# trsv_main.net
KiCad netlist of a schematic drawn in Altium Designer
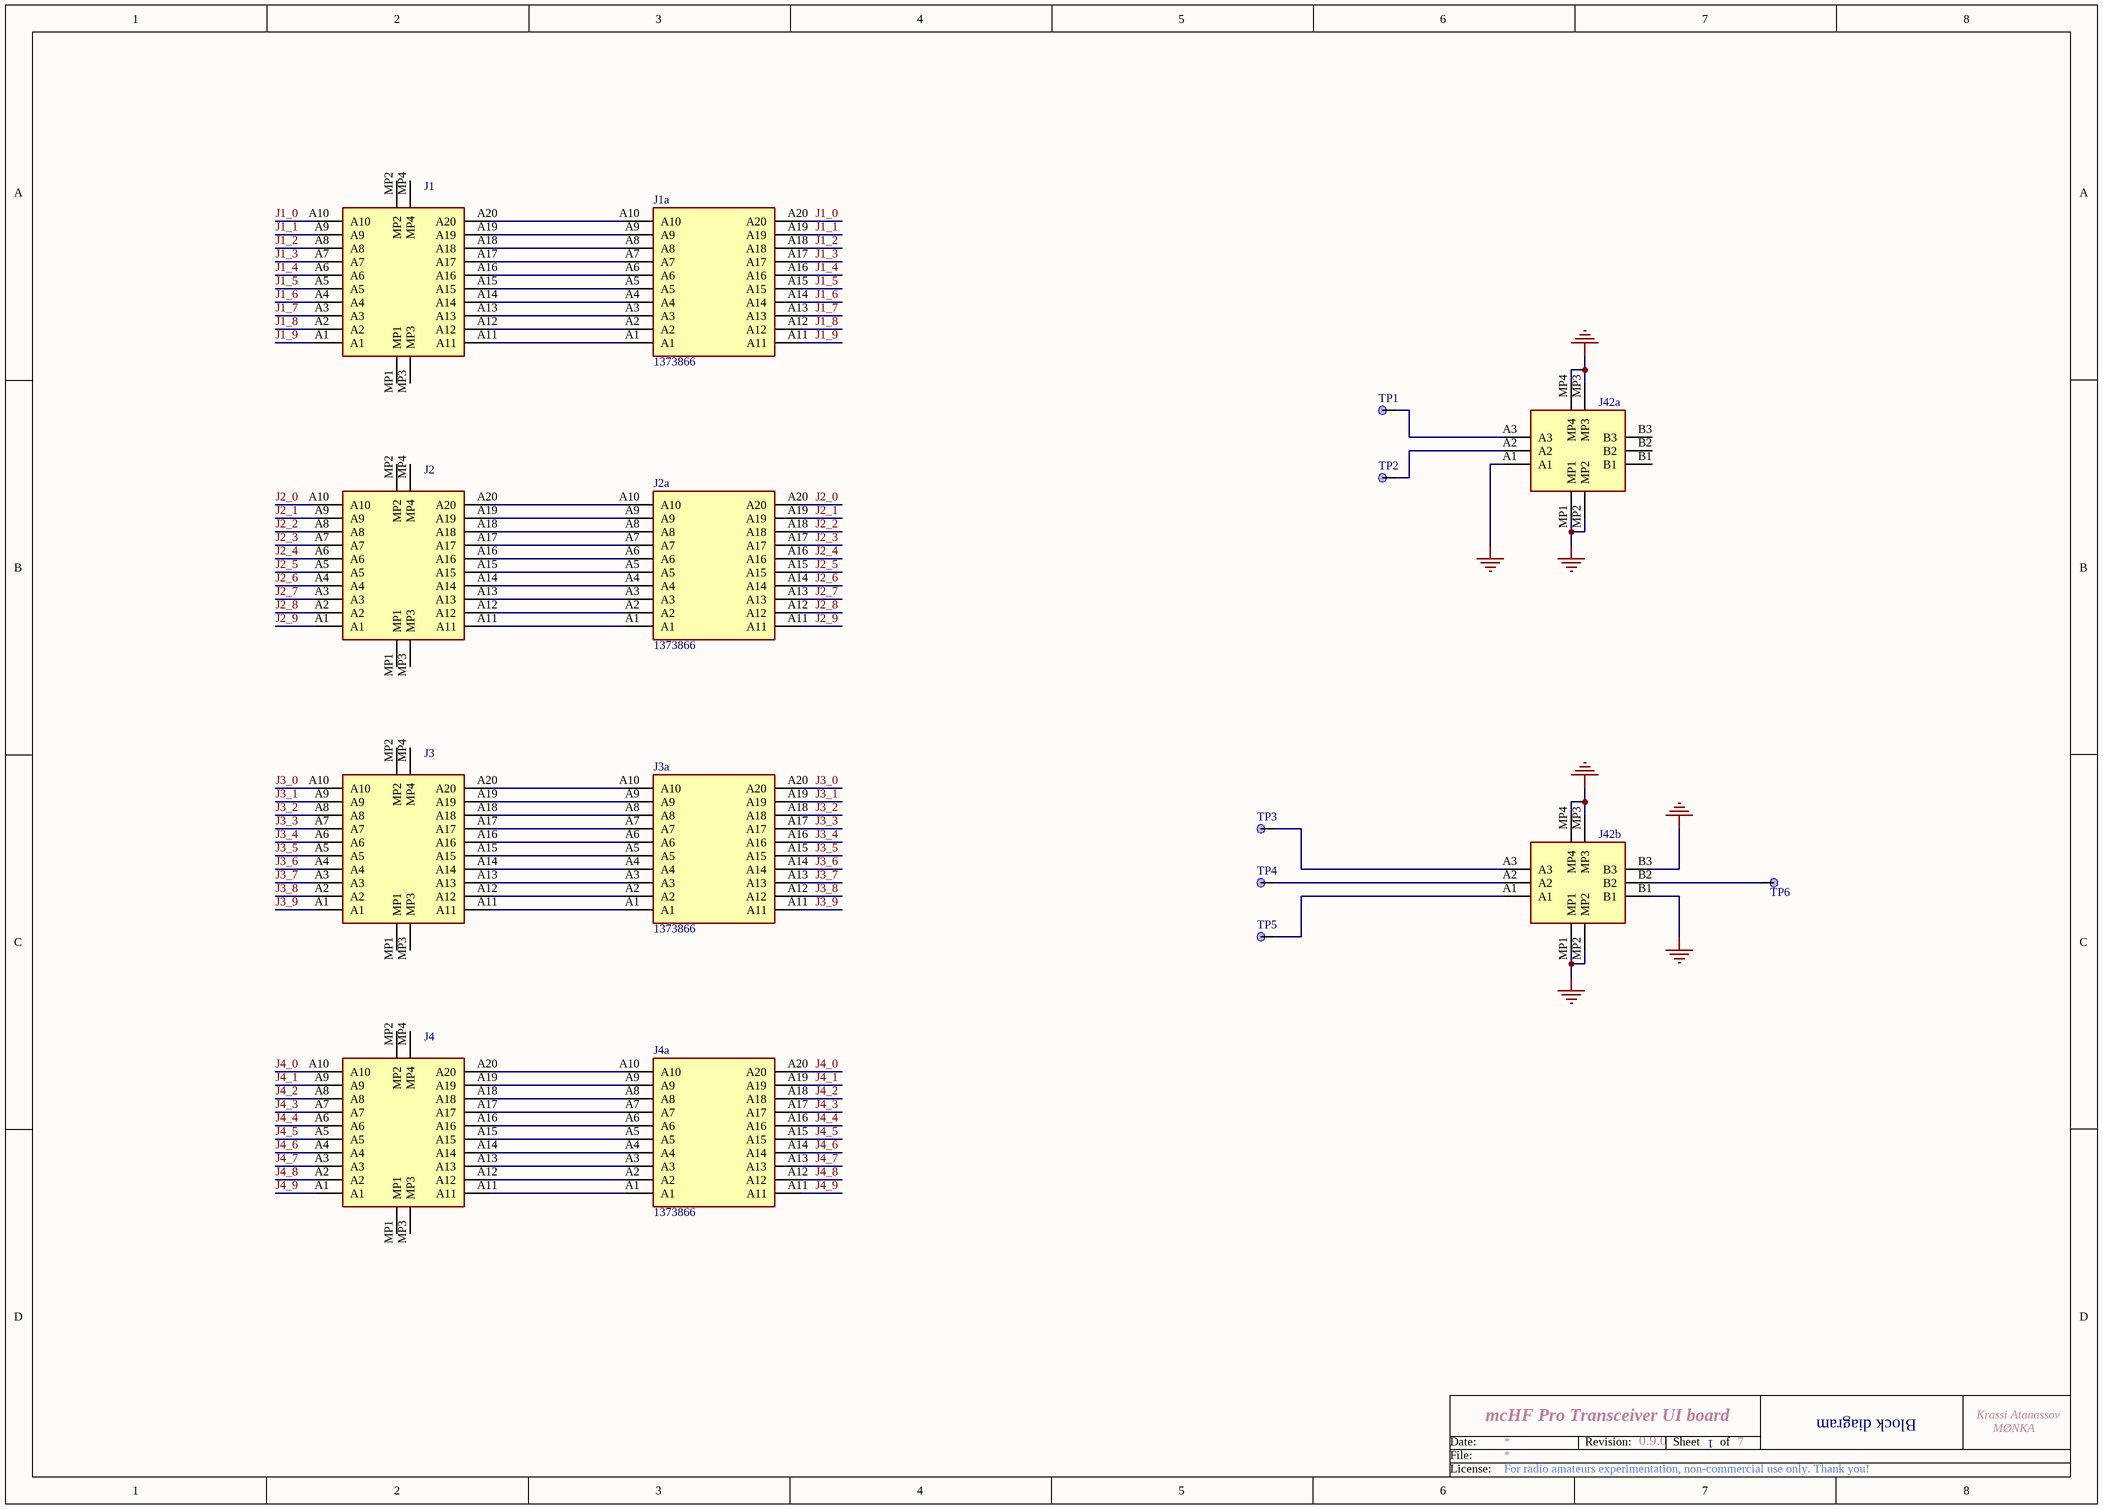
[diagram p0: trsv_main.SchDoc]

(export (version "E")
  (design (tool "Eeschema 10.0.6"))
  (components
    (comp (ref "J1")
      (value "1373866")
      (footprint "1373866")
      (fields (field (name "MOUSER PART NUMBER") "651-1373866"))
      (libsource (lib "1373866") (part "1373866"))
    )
    (comp (ref "J1a")
      (value "1373866")
      (footprint "YuanQi4mm")
      (fields (field (name "MOUSER PART NUMBER") "651-1373866"))
      (libsource (lib "__rf") (part "YQ_20p"))
    )
    (comp (ref "J2")
      (value "1373866")
      (footprint "1373866")
      (fields (field (name "MOUSER PART NUMBER") "651-1373866"))
      (libsource (lib "1373866") (part "1373866"))
    )
    (comp (ref "J2a")
      (value "1373866")
      (footprint "YuanQi4mm")
      (fields (field (name "MOUSER PART NUMBER") "651-1373866"))
      (libsource (lib "__rf") (part "YQ_20p"))
    )
    (comp (ref "J3")
      (value "1373866")
      (footprint "1373866")
      (fields (field (name "MOUSER PART NUMBER") "651-1373866"))
      (libsource (lib "1373866") (part "1373866"))
    )
    (comp (ref "J3a")
      (value "1373866")
      (footprint "YuanQi4mm")
      (fields (field (name "MOUSER PART NUMBER") "651-1373866"))
      (libsource (lib "__rf") (part "YQ_20p"))
    )
    (comp (ref "J4")
      (value "1373866")
      (footprint "1373866")
      (fields (field (name "MOUSER PART NUMBER") "651-1373866"))
      (libsource (lib "1373866") (part "1373866"))
    )
    (comp (ref "J4a")
      (value "1373866")
      (footprint "YuanQi4mm")
      (fields (field (name "MOUSER PART NUMBER") "651-1373866"))
      (libsource (lib "__rf") (part "YQ_20p"))
    )
    (comp (ref "J42a")
      (value "1373826")
      (footprint "1373826")
      (fields (field (name "MOUSER PART NUMBER") "651-1373826"))
      (libsource (lib "1373826") (part "1373826"))
    )
    (comp (ref "J42b")
      (value "1373826")
      (footprint "1373826")
      (fields (field (name "MOUSER PART NUMBER") "651-1373826"))
      (libsource (lib "1373826") (part "1373826"))
    )
    (comp (ref "TP1") (value "TP") (footprint "TP") (libsource (lib "__ui") (part "TP")))
    (comp (ref "TP2") (value "TP") (footprint "TP") (libsource (lib "__ui") (part "TP")))
    (comp (ref "TP3") (value "TP") (footprint "TP") (libsource (lib "__ui") (part "TP")))
    (comp (ref "TP4") (value "TP") (footprint "TP") (libsource (lib "__ui") (part "TP")))
    (comp (ref "TP5") (value "TP") (footprint "TP") (libsource (lib "__ui") (part "TP")))
    (comp (ref "TP6") (value "TP") (footprint "TP") (libsource (lib "__ui") (part "TP")))
  )
  (nets
    (net (code "1") (name "/J1_0") (class "Default")
      (node (ref "J1") (pin "A10") (pinfunction "A10_A10") (pintype "passive"))
      (node (ref "J1a") (pin "A20") (pinfunction "A20_A20") (pintype "passive"))
    )
    (net (code "2") (name "/J1_1") (class "Default")
      (node (ref "J1") (pin "A9") (pinfunction "A9_A9") (pintype "passive"))
      (node (ref "J1a") (pin "A19") (pinfunction "A19_A19") (pintype "passive"))
    )
    (net (code "3") (name "/J1_2") (class "Default")
      (node (ref "J1") (pin "A8") (pinfunction "A8_A8") (pintype "passive"))
      (node (ref "J1a") (pin "A18") (pinfunction "A18_A18") (pintype "passive"))
    )
    (net (code "4") (name "/J1_3") (class "Default")
      (node (ref "J1") (pin "A7") (pinfunction "A7_A7") (pintype "passive"))
      (node (ref "J1a") (pin "A17") (pinfunction "A17_A17") (pintype "passive"))
    )
    (net (code "5") (name "/J1_4") (class "Default")
      (node (ref "J1") (pin "A6") (pinfunction "A6_A6") (pintype "passive"))
      (node (ref "J1a") (pin "A16") (pinfunction "A16_A16") (pintype "passive"))
    )
    (net (code "6") (name "/J1_5") (class "Default")
      (node (ref "J1") (pin "A5") (pinfunction "A5_A5") (pintype "passive"))
      (node (ref "J1a") (pin "A15") (pinfunction "A15_A15") (pintype "passive"))
    )
    (net (code "7") (name "/J1_6") (class "Default")
      (node (ref "J1") (pin "A4") (pinfunction "A4_A4") (pintype "passive"))
      (node (ref "J1a") (pin "A14") (pinfunction "A14_A14") (pintype "passive"))
    )
    (net (code "8") (name "/J1_7") (class "Default")
      (node (ref "J1") (pin "A3") (pinfunction "A3_A3") (pintype "passive"))
      (node (ref "J1a") (pin "A13") (pinfunction "A13_A13") (pintype "passive"))
    )
    (net (code "9") (name "/J1_8") (class "Default")
      (node (ref "J1") (pin "A2") (pinfunction "A2_A2") (pintype "passive"))
      (node (ref "J1a") (pin "A12") (pinfunction "A12_A12") (pintype "passive"))
    )
    (net (code "10") (name "/J1_9") (class "Default")
      (node (ref "J1") (pin "A1") (pinfunction "A1_A1") (pintype "passive"))
      (node (ref "J1a") (pin "A11") (pinfunction "A11_A11") (pintype "passive"))
    )
    (net (code "11") (name "/J2_0") (class "Default")
      (node (ref "J2") (pin "A10") (pinfunction "A10_A10") (pintype "passive"))
      (node (ref "J2a") (pin "A20") (pinfunction "A20_A20") (pintype "passive"))
    )
    (net (code "12") (name "/J2_1") (class "Default")
      (node (ref "J2") (pin "A9") (pinfunction "A9_A9") (pintype "passive"))
      (node (ref "J2a") (pin "A19") (pinfunction "A19_A19") (pintype "passive"))
    )
    (net (code "13") (name "/J2_2") (class "Default")
      (node (ref "J2") (pin "A8") (pinfunction "A8_A8") (pintype "passive"))
      (node (ref "J2a") (pin "A18") (pinfunction "A18_A18") (pintype "passive"))
    )
    (net (code "14") (name "/J2_3") (class "Default")
      (node (ref "J2") (pin "A7") (pinfunction "A7_A7") (pintype "passive"))
      (node (ref "J2a") (pin "A17") (pinfunction "A17_A17") (pintype "passive"))
    )
    (net (code "15") (name "/J2_4") (class "Default")
      (node (ref "J2") (pin "A6") (pinfunction "A6_A6") (pintype "passive"))
      (node (ref "J2a") (pin "A16") (pinfunction "A16_A16") (pintype "passive"))
    )
    (net (code "16") (name "/J2_5") (class "Default")
      (node (ref "J2") (pin "A5") (pinfunction "A5_A5") (pintype "passive"))
      (node (ref "J2a") (pin "A15") (pinfunction "A15_A15") (pintype "passive"))
    )
    (net (code "17") (name "/J2_6") (class "Default")
      (node (ref "J2") (pin "A4") (pinfunction "A4_A4") (pintype "passive"))
      (node (ref "J2a") (pin "A14") (pinfunction "A14_A14") (pintype "passive"))
    )
    (net (code "18") (name "/J2_7") (class "Default")
      (node (ref "J2") (pin "A3") (pinfunction "A3_A3") (pintype "passive"))
      (node (ref "J2a") (pin "A13") (pinfunction "A13_A13") (pintype "passive"))
    )
    (net (code "19") (name "/J2_8") (class "Default")
      (node (ref "J2") (pin "A2") (pinfunction "A2_A2") (pintype "passive"))
      (node (ref "J2a") (pin "A12") (pinfunction "A12_A12") (pintype "passive"))
    )
    (net (code "20") (name "/J2_9") (class "Default")
      (node (ref "J2") (pin "A1") (pinfunction "A1_A1") (pintype "passive"))
      (node (ref "J2a") (pin "A11") (pinfunction "A11_A11") (pintype "passive"))
    )
    (net (code "21") (name "/J3_0") (class "Default")
      (node (ref "J3") (pin "A10") (pinfunction "A10_A10") (pintype "passive"))
      (node (ref "J3a") (pin "A20") (pinfunction "A20_A20") (pintype "passive"))
    )
    (net (code "22") (name "/J3_1") (class "Default")
      (node (ref "J3") (pin "A9") (pinfunction "A9_A9") (pintype "passive"))
      (node (ref "J3a") (pin "A19") (pinfunction "A19_A19") (pintype "passive"))
    )
    (net (code "23") (name "/J3_2") (class "Default")
      (node (ref "J3") (pin "A8") (pinfunction "A8_A8") (pintype "passive"))
      (node (ref "J3a") (pin "A18") (pinfunction "A18_A18") (pintype "passive"))
    )
    (net (code "24") (name "/J3_3") (class "Default")
      (node (ref "J3") (pin "A7") (pinfunction "A7_A7") (pintype "passive"))
      (node (ref "J3a") (pin "A17") (pinfunction "A17_A17") (pintype "passive"))
    )
    (net (code "25") (name "/J3_4") (class "Default")
      (node (ref "J3") (pin "A6") (pinfunction "A6_A6") (pintype "passive"))
      (node (ref "J3a") (pin "A16") (pinfunction "A16_A16") (pintype "passive"))
    )
    (net (code "26") (name "/J3_5") (class "Default")
      (node (ref "J3") (pin "A5") (pinfunction "A5_A5") (pintype "passive"))
      (node (ref "J3a") (pin "A15") (pinfunction "A15_A15") (pintype "passive"))
    )
    (net (code "27") (name "/J3_6") (class "Default")
      (node (ref "J3") (pin "A4") (pinfunction "A4_A4") (pintype "passive"))
      (node (ref "J3a") (pin "A14") (pinfunction "A14_A14") (pintype "passive"))
    )
    (net (code "28") (name "/J3_7") (class "Default")
      (node (ref "J3") (pin "A3") (pinfunction "A3_A3") (pintype "passive"))
      (node (ref "J3a") (pin "A13") (pinfunction "A13_A13") (pintype "passive"))
    )
    (net (code "29") (name "/J3_8") (class "Default")
      (node (ref "J3") (pin "A2") (pinfunction "A2_A2") (pintype "passive"))
      (node (ref "J3a") (pin "A12") (pinfunction "A12_A12") (pintype "passive"))
    )
    (net (code "30") (name "/J3_9") (class "Default")
      (node (ref "J3") (pin "A1") (pinfunction "A1_A1") (pintype "passive"))
      (node (ref "J3a") (pin "A11") (pinfunction "A11_A11") (pintype "passive"))
    )
    (net (code "31") (name "/J4_0") (class "Default")
      (node (ref "J4") (pin "A10") (pinfunction "A10_A10") (pintype "passive"))
      (node (ref "J4a") (pin "A20") (pinfunction "A20_A20") (pintype "passive"))
    )
    (net (code "32") (name "/J4_1") (class "Default")
      (node (ref "J4") (pin "A9") (pinfunction "A9_A9") (pintype "passive"))
      (node (ref "J4a") (pin "A19") (pinfunction "A19_A19") (pintype "passive"))
    )
    (net (code "33") (name "/J4_2") (class "Default")
      (node (ref "J4") (pin "A8") (pinfunction "A8_A8") (pintype "passive"))
      (node (ref "J4a") (pin "A18") (pinfunction "A18_A18") (pintype "passive"))
    )
    (net (code "34") (name "/J4_3") (class "Default")
      (node (ref "J4") (pin "A7") (pinfunction "A7_A7") (pintype "passive"))
      (node (ref "J4a") (pin "A17") (pinfunction "A17_A17") (pintype "passive"))
    )
    (net (code "35") (name "/J4_4") (class "Default")
      (node (ref "J4") (pin "A6") (pinfunction "A6_A6") (pintype "passive"))
      (node (ref "J4a") (pin "A16") (pinfunction "A16_A16") (pintype "passive"))
    )
    (net (code "36") (name "/J4_5") (class "Default")
      (node (ref "J4") (pin "A5") (pinfunction "A5_A5") (pintype "passive"))
      (node (ref "J4a") (pin "A15") (pinfunction "A15_A15") (pintype "passive"))
    )
    (net (code "37") (name "/J4_6") (class "Default")
      (node (ref "J4") (pin "A4") (pinfunction "A4_A4") (pintype "passive"))
      (node (ref "J4a") (pin "A14") (pinfunction "A14_A14") (pintype "passive"))
    )
    (net (code "38") (name "/J4_7") (class "Default")
      (node (ref "J4") (pin "A3") (pinfunction "A3_A3") (pintype "passive"))
      (node (ref "J4a") (pin "A13") (pinfunction "A13_A13") (pintype "passive"))
    )
    (net (code "39") (name "/J4_8") (class "Default")
      (node (ref "J4") (pin "A2") (pinfunction "A2_A2") (pintype "passive"))
      (node (ref "J4a") (pin "A12") (pinfunction "A12_A12") (pintype "passive"))
    )
    (net (code "40") (name "/J4_9") (class "Default")
      (node (ref "J4") (pin "A1") (pinfunction "A1_A1") (pintype "passive"))
      (node (ref "J4a") (pin "A11") (pinfunction "A11_A11") (pintype "passive"))
    )
    (net (code "41") (name "GND") (class "Default")
      (node (ref "J42a") (pin "A1") (pinfunction "A1_A1") (pintype "passive"))
      (node (ref "J42a") (pin "MP1") (pinfunction "MP1_MP1") (pintype "passive"))
      (node (ref "J42a") (pin "MP2") (pinfunction "MP2_MP2") (pintype "passive"))
      (node (ref "J42a") (pin "MP3") (pinfunction "MP3_MP3") (pintype "passive"))
      (node (ref "J42a") (pin "MP4") (pinfunction "MP4_MP4") (pintype "passive"))
      (node (ref "J42b") (pin "B1") (pinfunction "B1_B1") (pintype "passive"))
      (node (ref "J42b") (pin "B3") (pinfunction "B3_B3") (pintype "passive"))
      (node (ref "J42b") (pin "MP1") (pinfunction "MP1_MP1") (pintype "passive"))
      (node (ref "J42b") (pin "MP2") (pinfunction "MP2_MP2") (pintype "passive"))
      (node (ref "J42b") (pin "MP3") (pinfunction "MP3_MP3") (pintype "passive"))
      (node (ref "J42b") (pin "MP4") (pinfunction "MP4_MP4") (pintype "passive"))
    )
    (net (code "42") (name "Net-(J1-PadA11)") (class "Default")
      (node (ref "J1") (pin "A11") (pinfunction "A11_A11") (pintype "passive"))
      (node (ref "J1a") (pin "A1") (pinfunction "A1_A1") (pintype "passive"))
    )
    (net (code "43") (name "Net-(J1-PadA12)") (class "Default")
      (node (ref "J1") (pin "A12") (pinfunction "A12_A12") (pintype "passive"))
      (node (ref "J1a") (pin "A2") (pinfunction "A2_A2") (pintype "passive"))
    )
    (net (code "44") (name "Net-(J1-PadA13)") (class "Default")
      (node (ref "J1") (pin "A13") (pinfunction "A13_A13") (pintype "passive"))
      (node (ref "J1a") (pin "A3") (pinfunction "A3_A3") (pintype "passive"))
    )
    (net (code "45") (name "Net-(J1-PadA14)") (class "Default")
      (node (ref "J1") (pin "A14") (pinfunction "A14_A14") (pintype "passive"))
      (node (ref "J1a") (pin "A4") (pinfunction "A4_A4") (pintype "passive"))
    )
    (net (code "46") (name "Net-(J1-PadA15)") (class "Default")
      (node (ref "J1") (pin "A15") (pinfunction "A15_A15") (pintype "passive"))
      (node (ref "J1a") (pin "A5") (pinfunction "A5_A5") (pintype "passive"))
    )
    (net (code "47") (name "Net-(J1-PadA16)") (class "Default")
      (node (ref "J1") (pin "A16") (pinfunction "A16_A16") (pintype "passive"))
      (node (ref "J1a") (pin "A6") (pinfunction "A6_A6") (pintype "passive"))
    )
    (net (code "48") (name "Net-(J1-PadA17)") (class "Default")
      (node (ref "J1") (pin "A17") (pinfunction "A17_A17") (pintype "passive"))
      (node (ref "J1a") (pin "A7") (pinfunction "A7_A7") (pintype "passive"))
    )
    (net (code "49") (name "Net-(J1-PadA18)") (class "Default")
      (node (ref "J1") (pin "A18") (pinfunction "A18_A18") (pintype "passive"))
      (node (ref "J1a") (pin "A8") (pinfunction "A8_A8") (pintype "passive"))
    )
    (net (code "50") (name "Net-(J1-PadA19)") (class "Default")
      (node (ref "J1") (pin "A19") (pinfunction "A19_A19") (pintype "passive"))
      (node (ref "J1a") (pin "A9") (pinfunction "A9_A9") (pintype "passive"))
    )
    (net (code "51") (name "Net-(J1-PadA20)") (class "Default")
      (node (ref "J1") (pin "A20") (pinfunction "A20_A20") (pintype "passive"))
      (node (ref "J1a") (pin "A10") (pinfunction "A10_A10") (pintype "passive"))
    )
    (net (code "52") (name "Net-(J2-PadA11)") (class "Default")
      (node (ref "J2") (pin "A11") (pinfunction "A11_A11") (pintype "passive"))
      (node (ref "J2a") (pin "A1") (pinfunction "A1_A1") (pintype "passive"))
    )
    (net (code "53") (name "Net-(J2-PadA12)") (class "Default")
      (node (ref "J2") (pin "A12") (pinfunction "A12_A12") (pintype "passive"))
      (node (ref "J2a") (pin "A2") (pinfunction "A2_A2") (pintype "passive"))
    )
    (net (code "54") (name "Net-(J2-PadA13)") (class "Default")
      (node (ref "J2") (pin "A13") (pinfunction "A13_A13") (pintype "passive"))
      (node (ref "J2a") (pin "A3") (pinfunction "A3_A3") (pintype "passive"))
    )
    (net (code "55") (name "Net-(J2-PadA14)") (class "Default")
      (node (ref "J2") (pin "A14") (pinfunction "A14_A14") (pintype "passive"))
      (node (ref "J2a") (pin "A4") (pinfunction "A4_A4") (pintype "passive"))
    )
    (net (code "56") (name "Net-(J2-PadA15)") (class "Default")
      (node (ref "J2") (pin "A15") (pinfunction "A15_A15") (pintype "passive"))
      (node (ref "J2a") (pin "A5") (pinfunction "A5_A5") (pintype "passive"))
    )
    (net (code "57") (name "Net-(J2-PadA16)") (class "Default")
      (node (ref "J2") (pin "A16") (pinfunction "A16_A16") (pintype "passive"))
      (node (ref "J2a") (pin "A6") (pinfunction "A6_A6") (pintype "passive"))
    )
    (net (code "58") (name "Net-(J2-PadA17)") (class "Default")
      (node (ref "J2") (pin "A17") (pinfunction "A17_A17") (pintype "passive"))
      (node (ref "J2a") (pin "A7") (pinfunction "A7_A7") (pintype "passive"))
    )
    (net (code "59") (name "Net-(J2-PadA18)") (class "Default")
      (node (ref "J2") (pin "A18") (pinfunction "A18_A18") (pintype "passive"))
      (node (ref "J2a") (pin "A8") (pinfunction "A8_A8") (pintype "passive"))
    )
    (net (code "60") (name "Net-(J2-PadA19)") (class "Default")
      (node (ref "J2") (pin "A19") (pinfunction "A19_A19") (pintype "passive"))
      (node (ref "J2a") (pin "A9") (pinfunction "A9_A9") (pintype "passive"))
    )
    (net (code "61") (name "Net-(J2-PadA20)") (class "Default")
      (node (ref "J2") (pin "A20") (pinfunction "A20_A20") (pintype "passive"))
      (node (ref "J2a") (pin "A10") (pinfunction "A10_A10") (pintype "passive"))
    )
    (net (code "62") (name "Net-(J3-PadA11)") (class "Default")
      (node (ref "J3") (pin "A11") (pinfunction "A11_A11") (pintype "passive"))
      (node (ref "J3a") (pin "A1") (pinfunction "A1_A1") (pintype "passive"))
    )
    (net (code "63") (name "Net-(J3-PadA12)") (class "Default")
      (node (ref "J3") (pin "A12") (pinfunction "A12_A12") (pintype "passive"))
      (node (ref "J3a") (pin "A2") (pinfunction "A2_A2") (pintype "passive"))
    )
    (net (code "64") (name "Net-(J3-PadA13)") (class "Default")
      (node (ref "J3") (pin "A13") (pinfunction "A13_A13") (pintype "passive"))
      (node (ref "J3a") (pin "A3") (pinfunction "A3_A3") (pintype "passive"))
    )
    (net (code "65") (name "Net-(J3-PadA14)") (class "Default")
      (node (ref "J3") (pin "A14") (pinfunction "A14_A14") (pintype "passive"))
      (node (ref "J3a") (pin "A4") (pinfunction "A4_A4") (pintype "passive"))
    )
    (net (code "66") (name "Net-(J3-PadA15)") (class "Default")
      (node (ref "J3") (pin "A15") (pinfunction "A15_A15") (pintype "passive"))
      (node (ref "J3a") (pin "A5") (pinfunction "A5_A5") (pintype "passive"))
    )
    (net (code "67") (name "Net-(J3-PadA16)") (class "Default")
      (node (ref "J3") (pin "A16") (pinfunction "A16_A16") (pintype "passive"))
      (node (ref "J3a") (pin "A6") (pinfunction "A6_A6") (pintype "passive"))
    )
    (net (code "68") (name "Net-(J3-PadA17)") (class "Default")
      (node (ref "J3") (pin "A17") (pinfunction "A17_A17") (pintype "passive"))
      (node (ref "J3a") (pin "A7") (pinfunction "A7_A7") (pintype "passive"))
    )
    (net (code "69") (name "Net-(J3-PadA18)") (class "Default")
      (node (ref "J3") (pin "A18") (pinfunction "A18_A18") (pintype "passive"))
      (node (ref "J3a") (pin "A8") (pinfunction "A8_A8") (pintype "passive"))
    )
    (net (code "70") (name "Net-(J3-PadA19)") (class "Default")
      (node (ref "J3") (pin "A19") (pinfunction "A19_A19") (pintype "passive"))
      (node (ref "J3a") (pin "A9") (pinfunction "A9_A9") (pintype "passive"))
    )
    (net (code "71") (name "Net-(J3-PadA20)") (class "Default")
      (node (ref "J3") (pin "A20") (pinfunction "A20_A20") (pintype "passive"))
      (node (ref "J3a") (pin "A10") (pinfunction "A10_A10") (pintype "passive"))
    )
    (net (code "72") (name "Net-(J4-PadA11)") (class "Default")
      (node (ref "J4") (pin "A11") (pinfunction "A11_A11") (pintype "passive"))
      (node (ref "J4a") (pin "A1") (pinfunction "A1_A1") (pintype "passive"))
    )
    (net (code "73") (name "Net-(J4-PadA12)") (class "Default")
      (node (ref "J4") (pin "A12") (pinfunction "A12_A12") (pintype "passive"))
      (node (ref "J4a") (pin "A2") (pinfunction "A2_A2") (pintype "passive"))
    )
    (net (code "74") (name "Net-(J4-PadA13)") (class "Default")
      (node (ref "J4") (pin "A13") (pinfunction "A13_A13") (pintype "passive"))
      (node (ref "J4a") (pin "A3") (pinfunction "A3_A3") (pintype "passive"))
    )
    (net (code "75") (name "Net-(J4-PadA14)") (class "Default")
      (node (ref "J4") (pin "A14") (pinfunction "A14_A14") (pintype "passive"))
      (node (ref "J4a") (pin "A4") (pinfunction "A4_A4") (pintype "passive"))
    )
    (net (code "76") (name "Net-(J4-PadA15)") (class "Default")
      (node (ref "J4") (pin "A15") (pinfunction "A15_A15") (pintype "passive"))
      (node (ref "J4a") (pin "A5") (pinfunction "A5_A5") (pintype "passive"))
    )
    (net (code "77") (name "Net-(J4-PadA16)") (class "Default")
      (node (ref "J4") (pin "A16") (pinfunction "A16_A16") (pintype "passive"))
      (node (ref "J4a") (pin "A6") (pinfunction "A6_A6") (pintype "passive"))
    )
    (net (code "78") (name "Net-(J4-PadA17)") (class "Default")
      (node (ref "J4") (pin "A17") (pinfunction "A17_A17") (pintype "passive"))
      (node (ref "J4a") (pin "A7") (pinfunction "A7_A7") (pintype "passive"))
    )
    (net (code "79") (name "Net-(J4-PadA18)") (class "Default")
      (node (ref "J4") (pin "A18") (pinfunction "A18_A18") (pintype "passive"))
      (node (ref "J4a") (pin "A8") (pinfunction "A8_A8") (pintype "passive"))
    )
    (net (code "80") (name "Net-(J4-PadA19)") (class "Default")
      (node (ref "J4") (pin "A19") (pinfunction "A19_A19") (pintype "passive"))
      (node (ref "J4a") (pin "A9") (pinfunction "A9_A9") (pintype "passive"))
    )
    (net (code "81") (name "Net-(J4-PadA20)") (class "Default")
      (node (ref "J4") (pin "A20") (pinfunction "A20_A20") (pintype "passive"))
      (node (ref "J4a") (pin "A10") (pinfunction "A10_A10") (pintype "passive"))
    )
    (net (code "82") (name "Net-(J42a-PadA2)") (class "Default")
      (node (ref "J42a") (pin "A2") (pinfunction "A2_A2") (pintype "passive"))
      (node (ref "TP2") (pin "1") (pinfunction "1_1") (pintype "passive"))
    )
    (net (code "83") (name "Net-(J42a-PadA3)") (class "Default")
      (node (ref "J42a") (pin "A3") (pinfunction "A3_A3") (pintype "passive"))
      (node (ref "TP1") (pin "1") (pinfunction "1_1") (pintype "passive"))
    )
    (net (code "84") (name "Net-(J42b-PadA1)") (class "Default")
      (node (ref "J42b") (pin "A1") (pinfunction "A1_A1") (pintype "passive"))
      (node (ref "TP5") (pin "1") (pinfunction "1_1") (pintype "passive"))
    )
    (net (code "85") (name "Net-(J42b-PadA2)") (class "Default")
      (node (ref "J42b") (pin "A2") (pinfunction "A2_A2") (pintype "passive"))
      (node (ref "TP4") (pin "1") (pinfunction "1_1") (pintype "passive"))
    )
    (net (code "86") (name "Net-(J42b-PadA3)") (class "Default")
      (node (ref "J42b") (pin "A3") (pinfunction "A3_A3") (pintype "passive"))
      (node (ref "TP3") (pin "1") (pinfunction "1_1") (pintype "passive"))
    )
    (net (code "87") (name "Net-(J42b-PadB2)") (class "Default")
      (node (ref "J42b") (pin "B2") (pinfunction "B2_B2") (pintype "passive"))
      (node (ref "TP6") (pin "1") (pinfunction "1_1") (pintype "passive"))
    )
    (net (code "88") (name "unconnected-(J1-PadMP1)") (class "Default")
      (node (ref "J1") (pin "MP1") (pinfunction "MP1_MP1") (pintype "passive"))
    )
    (net (code "89") (name "unconnected-(J1-PadMP2)") (class "Default")
      (node (ref "J1") (pin "MP2") (pinfunction "MP2_MP2") (pintype "passive"))
    )
    (net (code "90") (name "unconnected-(J1-PadMP3)") (class "Default")
      (node (ref "J1") (pin "MP3") (pinfunction "MP3_MP3") (pintype "passive"))
    )
    (net (code "91") (name "unconnected-(J1-PadMP4)") (class "Default")
      (node (ref "J1") (pin "MP4") (pinfunction "MP4_MP4") (pintype "passive"))
    )
    (net (code "92") (name "unconnected-(J2-PadMP1)") (class "Default")
      (node (ref "J2") (pin "MP1") (pinfunction "MP1_MP1") (pintype "passive"))
    )
    (net (code "93") (name "unconnected-(J2-PadMP2)") (class "Default")
      (node (ref "J2") (pin "MP2") (pinfunction "MP2_MP2") (pintype "passive"))
    )
    (net (code "94") (name "unconnected-(J2-PadMP3)") (class "Default")
      (node (ref "J2") (pin "MP3") (pinfunction "MP3_MP3") (pintype "passive"))
    )
    (net (code "95") (name "unconnected-(J2-PadMP4)") (class "Default")
      (node (ref "J2") (pin "MP4") (pinfunction "MP4_MP4") (pintype "passive"))
    )
    (net (code "96") (name "unconnected-(J3-PadMP1)") (class "Default")
      (node (ref "J3") (pin "MP1") (pinfunction "MP1_MP1") (pintype "passive"))
    )
    (net (code "97") (name "unconnected-(J3-PadMP2)") (class "Default")
      (node (ref "J3") (pin "MP2") (pinfunction "MP2_MP2") (pintype "passive"))
    )
    (net (code "98") (name "unconnected-(J3-PadMP3)") (class "Default")
      (node (ref "J3") (pin "MP3") (pinfunction "MP3_MP3") (pintype "passive"))
    )
    (net (code "99") (name "unconnected-(J3-PadMP4)") (class "Default")
      (node (ref "J3") (pin "MP4") (pinfunction "MP4_MP4") (pintype "passive"))
    )
    (net (code "100") (name "unconnected-(J4-PadMP1)") (class "Default")
      (node (ref "J4") (pin "MP1") (pinfunction "MP1_MP1") (pintype "passive"))
    )
    (net (code "101") (name "unconnected-(J4-PadMP2)") (class "Default")
      (node (ref "J4") (pin "MP2") (pinfunction "MP2_MP2") (pintype "passive"))
    )
    (net (code "102") (name "unconnected-(J4-PadMP3)") (class "Default")
      (node (ref "J4") (pin "MP3") (pinfunction "MP3_MP3") (pintype "passive"))
    )
    (net (code "103") (name "unconnected-(J4-PadMP4)") (class "Default")
      (node (ref "J4") (pin "MP4") (pinfunction "MP4_MP4") (pintype "passive"))
    )
    (net (code "104") (name "unconnected-(J42a-PadB1)") (class "Default")
      (node (ref "J42a") (pin "B1") (pinfunction "B1_B1") (pintype "passive"))
    )
    (net (code "105") (name "unconnected-(J42a-PadB2)") (class "Default")
      (node (ref "J42a") (pin "B2") (pinfunction "B2_B2") (pintype "passive"))
    )
    (net (code "106") (name "unconnected-(J42a-PadB3)") (class "Default")
      (node (ref "J42a") (pin "B3") (pinfunction "B3_B3") (pintype "passive"))
    )
  )
)
